# Trilife_1.net
KiCad netlist of a schematic drawn in EAGLE
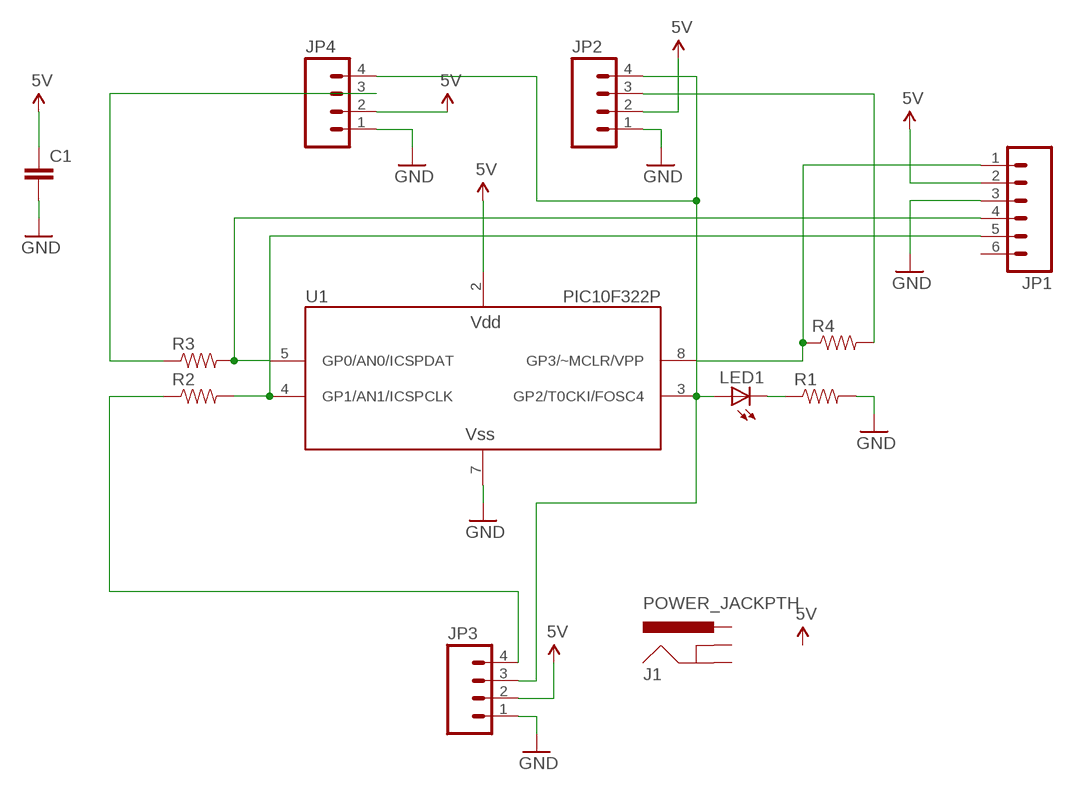
[diagram p0: schematic, sheet 1]

(export (version "E")
  (design (tool "Eeschema 10.0.6"))
  (components
    (comp (ref "C1")
      (value "CAPPTH")
      (footprint "eagle-import:CAP-PTH-SMALL")
      (libsource (lib "eagle-import") (part "CAPPTH"))
    )
    (comp (ref "J1")
      (value "POWER_JACKPTH")
      (footprint "eagle-import:POWER_JACK_PTH")
      (libsource (lib "eagle-import") (part "POWER_JACKPTH"))
    )
    (comp (ref "JP1")
      (value "M06LOCK")
      (footprint "eagle-import:1X06_LOCK")
      (libsource (lib "eagle-import") (part "M06LOCK"))
    )
    (comp (ref "JP2")
      (value "M04LOCK")
      (footprint "eagle-import:1X04_LOCK")
      (libsource (lib "eagle-import") (part "M04LOCK"))
    )
    (comp (ref "JP3")
      (value "M04LOCK")
      (footprint "eagle-import:1X04_LOCK")
      (libsource (lib "eagle-import") (part "M04LOCK"))
    )
    (comp (ref "JP4")
      (value "M04LOCK")
      (footprint "eagle-import:1X04_LOCK")
      (libsource (lib "eagle-import") (part "M04LOCK"))
    )
    (comp (ref "LED1")
      (value "LED5MM")
      (footprint "eagle-import:LED5MM")
      (libsource (lib "eagle-import") (part "LED5MM"))
    )
    (comp (ref "R1")
      (value "RESISTORPTH-1/4W")
      (footprint "eagle-import:AXIAL-0.4")
      (libsource (lib "eagle-import") (part "RESISTORPTH-1/4W"))
    )
    (comp (ref "R2")
      (value "RESISTORPTH-1/4W")
      (footprint "eagle-import:AXIAL-0.4")
      (libsource (lib "eagle-import") (part "RESISTORPTH-1/4W"))
    )
    (comp (ref "R3")
      (value "RESISTORPTH-1/4W")
      (footprint "eagle-import:AXIAL-0.4")
      (libsource (lib "eagle-import") (part "RESISTORPTH-1/4W"))
    )
    (comp (ref "R4")
      (value "RESISTORPTH-1/4W")
      (footprint "eagle-import:AXIAL-0.4")
      (libsource (lib "eagle-import") (part "RESISTORPTH-1/4W"))
    )
    (comp (ref "U1")
      (value "PIC10F322P")
      (footprint "eagle-import:DIP-8")
      (libsource (lib "eagle-import") (part "PIC10F32P2"))
    )
  )
  (nets
    (net (code "1") (name "5V") (class "Default")
      (node (ref "C1") (pin "1") (pinfunction "1_1") (pintype "passive"))
      (node (ref "JP1") (pin "2") (pinfunction "2_2") (pintype "passive"))
      (node (ref "JP2") (pin "2") (pinfunction "2_2") (pintype "passive"))
      (node (ref "JP3") (pin "2") (pinfunction "2_2") (pintype "passive"))
      (node (ref "JP4") (pin "2") (pinfunction "2_2") (pintype "passive"))
      (node (ref "U1") (pin "2") (pinfunction "VDD_2") (pintype "power_in"))
    )
    (net (code "2") (name "GND") (class "Default")
      (node (ref "C1") (pin "2") (pinfunction "2_2") (pintype "passive"))
      (node (ref "JP1") (pin "3") (pinfunction "3_3") (pintype "passive"))
      (node (ref "JP2") (pin "1") (pinfunction "1_1") (pintype "passive"))
      (node (ref "JP3") (pin "1") (pinfunction "1_1") (pintype "passive"))
      (node (ref "JP4") (pin "1") (pinfunction "1_1") (pintype "passive"))
      (node (ref "R1") (pin "P$2") (pinfunction "2_P$2") (pintype "passive"))
      (node (ref "U1") (pin "7") (pinfunction "VSS_7") (pintype "power_in"))
    )
    (net (code "3") (name "Net-(LED1-C)") (class "Default")
      (node (ref "LED1") (pin "K") (pinfunction "C_K") (pintype "passive"))
      (node (ref "R1") (pin "P$1") (pinfunction "1_P$1") (pintype "passive"))
    )
    (net (code "4") (name "Net-(R2-1)") (class "Default")
      (node (ref "JP3") (pin "4") (pinfunction "4_4") (pintype "passive"))
      (node (ref "R2") (pin "P$1") (pinfunction "1_P$1") (pintype "passive"))
    )
    (net (code "5") (name "Net-(R2-2)") (class "Default")
      (node (ref "JP1") (pin "5") (pinfunction "5_5") (pintype "passive"))
      (node (ref "R2") (pin "P$2") (pinfunction "2_P$2") (pintype "passive"))
      (node (ref "U1") (pin "4") (pinfunction "GP1/AN1/ICSPCLK_4") (pintype "bidirectional"))
    )
    (net (code "6") (name "Net-(R3-1)") (class "Default")
      (node (ref "JP4") (pin "3") (pinfunction "3_3") (pintype "passive"))
      (node (ref "R3") (pin "P$1") (pinfunction "1_P$1") (pintype "passive"))
    )
    (net (code "7") (name "Net-(R3-2)") (class "Default")
      (node (ref "JP1") (pin "4") (pinfunction "4_4") (pintype "passive"))
      (node (ref "R3") (pin "P$2") (pinfunction "2_P$2") (pintype "passive"))
      (node (ref "U1") (pin "5") (pinfunction "GP0/AN0/ICSPDAT_5") (pintype "bidirectional"))
    )
    (net (code "8") (name "Net-(R4-1)") (class "Default")
      (node (ref "JP1") (pin "1") (pinfunction "1_1") (pintype "passive"))
      (node (ref "R4") (pin "P$1") (pinfunction "1_P$1") (pintype "passive"))
      (node (ref "U1") (pin "8") (pinfunction "GP3/~{MCLR/VPP}_8") (pintype "input"))
    )
    (net (code "9") (name "Net-(R4-2)") (class "Default")
      (node (ref "JP2") (pin "3") (pinfunction "3_3") (pintype "passive"))
      (node (ref "R4") (pin "P$2") (pinfunction "2_P$2") (pintype "passive"))
    )
    (net (code "10") (name "Net-(U1-GP2{slash}T0CKI{slash}FOSC4)") (class "Default")
      (node (ref "JP2") (pin "4") (pinfunction "4_4") (pintype "passive"))
      (node (ref "JP3") (pin "3") (pinfunction "3_3") (pintype "passive"))
      (node (ref "JP4") (pin "4") (pinfunction "4_4") (pintype "passive"))
      (node (ref "LED1") (pin "A") (pinfunction "A_A") (pintype "passive"))
      (node (ref "U1") (pin "3") (pinfunction "GP2/T0CKI/FOSC4_3") (pintype "bidirectional"))
    )
    (net (code "11") (name "unconnected-(J1-PadGND)") (class "Default")
      (node (ref "J1") (pin "GND") (pinfunction "GND_GND") (pintype "bidirectional"))
    )
    (net (code "12") (name "unconnected-(J1-PadGNDBREAK)") (class "Default")
      (node (ref "J1") (pin "GNDBREAK") (pinfunction "GNDBREAK_GNDBREAK") (pintype "bidirectional"))
    )
    (net (code "13") (name "unconnected-(J1-PadPWR)") (class "Default")
      (node (ref "J1") (pin "PWR") (pinfunction "PWR_PWR") (pintype "bidirectional"))
    )
    (net (code "14") (name "unconnected-(JP1-Pad6)") (class "Default")
      (node (ref "JP1") (pin "6") (pinfunction "6_6") (pintype "passive"))
    )
  )
)
